# col_driver.net
KiCad netlist of a schematic drawn in EAGLE
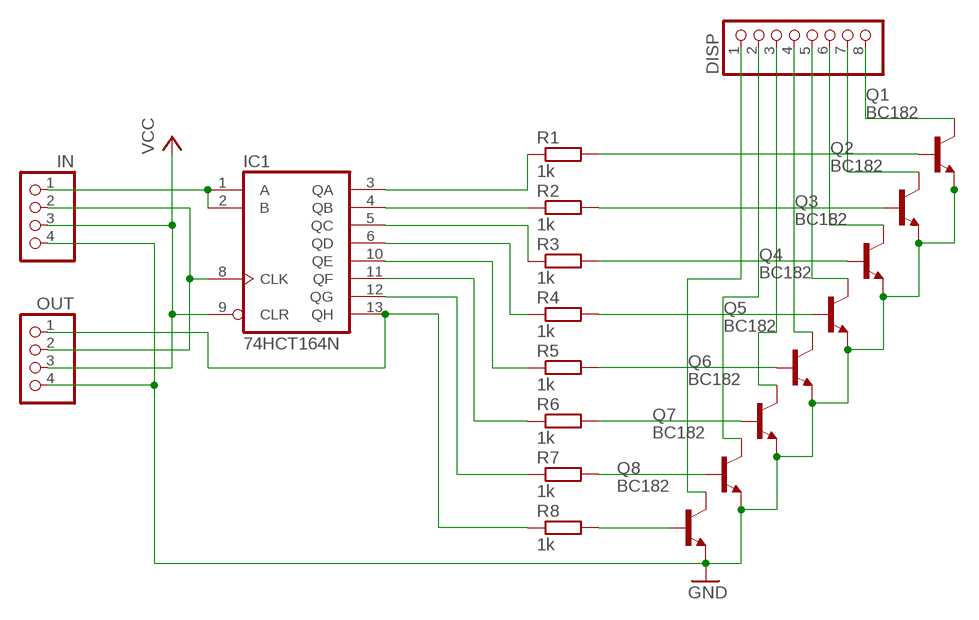
[diagram p0: schematic, sheet 1]

(export (version "E")
  (design (tool "Eeschema 10.0.6"))
  (components
    (comp (ref "DISP")
      (value "PINHD-1X8")
      (footprint "eagle-import:1X08")
      (libsource (lib "eagle-import") (part "PINHD-1X8"))
    )
    (comp (ref "IC1")
      (value "74HCT164N")
      (footprint "eagle-import:DIL14")
      (libsource (lib "eagle-import") (part "74164NHCT"))
    )
    (comp (ref "IN")
      (value "PINHD-1X4")
      (footprint "eagle-import:1X04")
      (libsource (lib "eagle-import") (part "PINHD-1X4"))
    )
    (comp (ref "OUT")
      (value "PINHD-1X4")
      (footprint "eagle-import:1X04")
      (libsource (lib "eagle-import") (part "PINHD-1X4"))
    )
    (comp (ref "Q1")
      (value "BC182")
      (footprint "eagle-import:TO92")
      (libsource (lib "eagle-import") (part "BC237"))
    )
    (comp (ref "Q2")
      (value "BC182")
      (footprint "eagle-import:TO92")
      (libsource (lib "eagle-import") (part "BC237"))
    )
    (comp (ref "Q3")
      (value "BC182")
      (footprint "eagle-import:TO92")
      (libsource (lib "eagle-import") (part "BC237"))
    )
    (comp (ref "Q4")
      (value "BC182")
      (footprint "eagle-import:TO92")
      (libsource (lib "eagle-import") (part "BC237"))
    )
    (comp (ref "Q5")
      (value "BC182")
      (footprint "eagle-import:TO92")
      (libsource (lib "eagle-import") (part "BC237"))
    )
    (comp (ref "Q6")
      (value "BC182")
      (footprint "eagle-import:TO92")
      (libsource (lib "eagle-import") (part "BC237"))
    )
    (comp (ref "Q7")
      (value "BC182")
      (footprint "eagle-import:TO92")
      (libsource (lib "eagle-import") (part "BC237"))
    )
    (comp (ref "Q8")
      (value "BC182")
      (footprint "eagle-import:TO92")
      (libsource (lib "eagle-import") (part "BC237"))
    )
    (comp (ref "R1")
      (value "1k")
      (footprint "eagle-import:0207_10")
      (libsource (lib "eagle-import") (part "R-EU_0207/10"))
    )
    (comp (ref "R2")
      (value "1k")
      (footprint "eagle-import:0207_10")
      (libsource (lib "eagle-import") (part "R-EU_0207/10"))
    )
    (comp (ref "R3")
      (value "1k")
      (footprint "eagle-import:0207_10")
      (libsource (lib "eagle-import") (part "R-EU_0207/10"))
    )
    (comp (ref "R4")
      (value "1k")
      (footprint "eagle-import:0207_10")
      (libsource (lib "eagle-import") (part "R-EU_0207/10"))
    )
    (comp (ref "R5")
      (value "1k")
      (footprint "eagle-import:0207_10")
      (libsource (lib "eagle-import") (part "R-EU_0207/10"))
    )
    (comp (ref "R6")
      (value "1k")
      (footprint "eagle-import:0207_10")
      (libsource (lib "eagle-import") (part "R-EU_0207/10"))
    )
    (comp (ref "R7")
      (value "1k")
      (footprint "eagle-import:0207_10")
      (libsource (lib "eagle-import") (part "R-EU_0207/10"))
    )
    (comp (ref "R8")
      (value "1k")
      (footprint "eagle-import:0207_10")
      (libsource (lib "eagle-import") (part "R-EU_0207/10"))
    )
  )
  (nets
    (net (code "1") (name "GND") (class "Default")
      (node (ref "IN") (pin "4") (pinfunction "4_4") (pintype "passive"))
      (node (ref "OUT") (pin "4") (pinfunction "4_4") (pintype "passive"))
      (node (ref "Q1") (pin "1") (pinfunction "E_1") (pintype "passive"))
      (node (ref "Q2") (pin "1") (pinfunction "E_1") (pintype "passive"))
      (node (ref "Q3") (pin "1") (pinfunction "E_1") (pintype "passive"))
      (node (ref "Q4") (pin "1") (pinfunction "E_1") (pintype "passive"))
      (node (ref "Q5") (pin "1") (pinfunction "E_1") (pintype "passive"))
      (node (ref "Q6") (pin "1") (pinfunction "E_1") (pintype "passive"))
      (node (ref "Q7") (pin "1") (pinfunction "E_1") (pintype "passive"))
      (node (ref "Q8") (pin "1") (pinfunction "E_1") (pintype "passive"))
    )
    (net (code "2") (name "Net-(IC1A-A)") (class "Default")
      (node (ref "IC1") (pin "1") (pinfunction "A_1") (pintype "input"))
      (node (ref "IC1") (pin "2") (pinfunction "B_2") (pintype "input"))
      (node (ref "IN") (pin "1") (pinfunction "1_1") (pintype "passive"))
    )
    (net (code "3") (name "Net-(IC1A-CLK)") (class "Default")
      (node (ref "IC1") (pin "8") (pinfunction "CLK_8") (pintype "input"))
      (node (ref "IN") (pin "2") (pinfunction "2_2") (pintype "passive"))
      (node (ref "OUT") (pin "2") (pinfunction "2_2") (pintype "passive"))
    )
    (net (code "4") (name "Net-(IC1A-QA)") (class "Default")
      (node (ref "IC1") (pin "3") (pinfunction "QA_3") (pintype "output"))
      (node (ref "R1") (pin "1") (pinfunction "1_1") (pintype "passive"))
    )
    (net (code "5") (name "Net-(IC1A-QB)") (class "Default")
      (node (ref "IC1") (pin "4") (pinfunction "QB_4") (pintype "output"))
      (node (ref "R2") (pin "1") (pinfunction "1_1") (pintype "passive"))
    )
    (net (code "6") (name "Net-(IC1A-QC)") (class "Default")
      (node (ref "IC1") (pin "5") (pinfunction "QC_5") (pintype "output"))
      (node (ref "R3") (pin "1") (pinfunction "1_1") (pintype "passive"))
    )
    (net (code "7") (name "Net-(IC1A-QD)") (class "Default")
      (node (ref "IC1") (pin "6") (pinfunction "QD_6") (pintype "output"))
      (node (ref "R4") (pin "1") (pinfunction "1_1") (pintype "passive"))
    )
    (net (code "8") (name "Net-(IC1A-QE)") (class "Default")
      (node (ref "IC1") (pin "10") (pinfunction "QE_10") (pintype "output"))
      (node (ref "R5") (pin "1") (pinfunction "1_1") (pintype "passive"))
    )
    (net (code "9") (name "Net-(IC1A-QF)") (class "Default")
      (node (ref "IC1") (pin "11") (pinfunction "QF_11") (pintype "output"))
      (node (ref "R6") (pin "1") (pinfunction "1_1") (pintype "passive"))
    )
    (net (code "10") (name "Net-(IC1A-QG)") (class "Default")
      (node (ref "IC1") (pin "12") (pinfunction "QG_12") (pintype "output"))
      (node (ref "R7") (pin "1") (pinfunction "1_1") (pintype "passive"))
    )
    (net (code "11") (name "Net-(IC1A-QH)") (class "Default")
      (node (ref "IC1") (pin "13") (pinfunction "QH_13") (pintype "output"))
      (node (ref "OUT") (pin "1") (pinfunction "1_1") (pintype "passive"))
      (node (ref "R8") (pin "1") (pinfunction "1_1") (pintype "passive"))
    )
    (net (code "12") (name "Net-(Q1-B)") (class "Default")
      (node (ref "Q1") (pin "2") (pinfunction "B_2") (pintype "passive"))
      (node (ref "R1") (pin "2") (pinfunction "2_2") (pintype "passive"))
    )
    (net (code "13") (name "Net-(Q1-C)") (class "Default")
      (node (ref "DISP") (pin "8") (pinfunction "8_8") (pintype "passive"))
      (node (ref "Q1") (pin "3") (pinfunction "C_3") (pintype "passive"))
    )
    (net (code "14") (name "Net-(Q2-B)") (class "Default")
      (node (ref "Q2") (pin "2") (pinfunction "B_2") (pintype "passive"))
      (node (ref "R2") (pin "2") (pinfunction "2_2") (pintype "passive"))
    )
    (net (code "15") (name "Net-(Q2-C)") (class "Default")
      (node (ref "DISP") (pin "7") (pinfunction "7_7") (pintype "passive"))
      (node (ref "Q2") (pin "3") (pinfunction "C_3") (pintype "passive"))
    )
    (net (code "16") (name "Net-(Q3-B)") (class "Default")
      (node (ref "Q3") (pin "2") (pinfunction "B_2") (pintype "passive"))
      (node (ref "R3") (pin "2") (pinfunction "2_2") (pintype "passive"))
    )
    (net (code "17") (name "Net-(Q3-C)") (class "Default")
      (node (ref "DISP") (pin "6") (pinfunction "6_6") (pintype "passive"))
      (node (ref "Q3") (pin "3") (pinfunction "C_3") (pintype "passive"))
    )
    (net (code "18") (name "Net-(Q4-B)") (class "Default")
      (node (ref "Q4") (pin "2") (pinfunction "B_2") (pintype "passive"))
      (node (ref "R4") (pin "2") (pinfunction "2_2") (pintype "passive"))
    )
    (net (code "19") (name "Net-(Q4-C)") (class "Default")
      (node (ref "DISP") (pin "5") (pinfunction "5_5") (pintype "passive"))
      (node (ref "Q4") (pin "3") (pinfunction "C_3") (pintype "passive"))
    )
    (net (code "20") (name "Net-(Q5-B)") (class "Default")
      (node (ref "Q5") (pin "2") (pinfunction "B_2") (pintype "passive"))
      (node (ref "R5") (pin "2") (pinfunction "2_2") (pintype "passive"))
    )
    (net (code "21") (name "Net-(Q5-C)") (class "Default")
      (node (ref "DISP") (pin "4") (pinfunction "4_4") (pintype "passive"))
      (node (ref "Q5") (pin "3") (pinfunction "C_3") (pintype "passive"))
    )
    (net (code "22") (name "Net-(Q6-B)") (class "Default")
      (node (ref "Q6") (pin "2") (pinfunction "B_2") (pintype "passive"))
      (node (ref "R6") (pin "2") (pinfunction "2_2") (pintype "passive"))
    )
    (net (code "23") (name "Net-(Q6-C)") (class "Default")
      (node (ref "DISP") (pin "3") (pinfunction "3_3") (pintype "passive"))
      (node (ref "Q6") (pin "3") (pinfunction "C_3") (pintype "passive"))
    )
    (net (code "24") (name "Net-(Q7-B)") (class "Default")
      (node (ref "Q7") (pin "2") (pinfunction "B_2") (pintype "passive"))
      (node (ref "R7") (pin "2") (pinfunction "2_2") (pintype "passive"))
    )
    (net (code "25") (name "Net-(Q7-C)") (class "Default")
      (node (ref "DISP") (pin "2") (pinfunction "2_2") (pintype "passive"))
      (node (ref "Q7") (pin "3") (pinfunction "C_3") (pintype "passive"))
    )
    (net (code "26") (name "Net-(Q8-B)") (class "Default")
      (node (ref "Q8") (pin "2") (pinfunction "B_2") (pintype "passive"))
      (node (ref "R8") (pin "2") (pinfunction "2_2") (pintype "passive"))
    )
    (net (code "27") (name "Net-(Q8-C)") (class "Default")
      (node (ref "DISP") (pin "1") (pinfunction "1_1") (pintype "passive"))
      (node (ref "Q8") (pin "3") (pinfunction "C_3") (pintype "passive"))
    )
    (net (code "28") (name "VCC") (class "Default")
      (node (ref "IC1") (pin "9") (pinfunction "CLR_9") (pintype "input"))
      (node (ref "IN") (pin "3") (pinfunction "3_3") (pintype "passive"))
      (node (ref "OUT") (pin "3") (pinfunction "3_3") (pintype "passive"))
    )
  )
)
